# cSLIM_uSD.net
KiCad netlist of a schematic drawn in Altium Designer
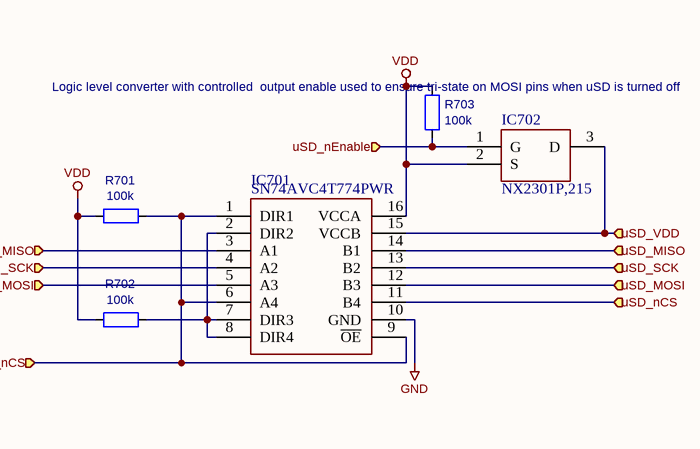
[diagram p0: cSLIM_uSD.SchDoc]

(export (version "E")
  (design (tool "Eeschema 10.0.6"))
  (components
    (comp (ref "IC701")
      (value "SN74AVC4T774PWR")
      (footprint "cSLIM-SA:SOP65P640X120-16N")
      (description "Integrated Circuit")
      (fields (field (name "MOUSER PART NUMBER") "595-SN74AVC4T774PWR"))
      (libsource (lib "cSLIM-SA") (part "SN74AVC4T774PWR"))
    )
    (comp (ref "IC702")
      (value "NX2301P,215")
      (footprint "cSLIM-SA:SOT95P230X110-3N")
      (description "Integrated Circuit")
      (fields (field (name "MOUSER PART NUMBER") "771-NX2301P215"))
      (libsource (lib "cSLIM-SA") (part "NX2301P,215"))
    )
    (comp (ref "R701") (value "100k") (footprint "RESC1608X55N") (libsource (lib "cSLIM-SA") (part "R")))
    (comp (ref "R702") (value "100k") (footprint "RESC1608X55N") (libsource (lib "cSLIM-SA") (part "R")))
    (comp (ref "R703") (value "100k") (footprint "RESC1608X55N") (libsource (lib "") (part "R_1")))
  )
  (nets
    (net (code "1") (name "/SPI_MISO") (class "Default")
      (node (ref "IC701") (pin "3") (pinfunction "A1_3") (pintype "passive"))
    )
    (net (code "2") (name "/SPI_MOSI") (class "Default")
      (node (ref "IC701") (pin "5") (pinfunction "A3_5") (pintype "passive"))
    )
    (net (code "3") (name "/SPI_SCK") (class "Default")
      (node (ref "IC701") (pin "4") (pinfunction "A2_4") (pintype "passive"))
    )
    (net (code "4") (name "/nRF_uSD_nCS") (class "Default")
      (node (ref "IC701") (pin "1") (pinfunction "DIR1_1") (pintype "passive"))
      (node (ref "IC701") (pin "6") (pinfunction "A4_6") (pintype "passive"))
      (node (ref "IC701") (pin "9") (pinfunction "~{OE}_9") (pintype "passive"))
      (node (ref "R701") (pin "1") (pinfunction "1_1") (pintype "passive"))
    )
    (net (code "5") (name "/uSD_MISO") (class "Default")
      (node (ref "IC701") (pin "14") (pinfunction "B1_14") (pintype "passive"))
    )
    (net (code "6") (name "/uSD_MOSI") (class "Default")
      (node (ref "IC701") (pin "12") (pinfunction "B3_12") (pintype "passive"))
    )
    (net (code "7") (name "/uSD_SCK") (class "Default")
      (node (ref "IC701") (pin "13") (pinfunction "B2_13") (pintype "passive"))
    )
    (net (code "8") (name "/uSD_VDD") (class "Default")
      (node (ref "IC701") (pin "15") (pinfunction "VCCB_15") (pintype "passive"))
      (node (ref "IC702") (pin "3") (pinfunction "D_3") (pintype "passive"))
    )
    (net (code "9") (name "/uSD_nCS") (class "Default")
      (node (ref "IC701") (pin "11") (pinfunction "B4_11") (pintype "passive"))
    )
    (net (code "10") (name "/uSD_nEnable") (class "Default")
      (node (ref "IC702") (pin "1") (pinfunction "G_1") (pintype "passive"))
      (node (ref "R703") (pin "1") (pinfunction "1_1") (pintype "passive"))
    )
    (net (code "11") (name "GND") (class "Default")
      (node (ref "IC701") (pin "10") (pinfunction "GND_10") (pintype "passive"))
    )
    (net (code "12") (name "Net-(IC701-DIR2)") (class "Default")
      (node (ref "IC701") (pin "2") (pinfunction "DIR2_2") (pintype "passive"))
      (node (ref "IC701") (pin "7") (pinfunction "DIR3_7") (pintype "passive"))
      (node (ref "IC701") (pin "8") (pinfunction "DIR4_8") (pintype "passive"))
      (node (ref "R702") (pin "1") (pinfunction "1_1") (pintype "passive"))
    )
    (net (code "13") (name "VDD") (class "Default")
      (node (ref "IC701") (pin "16") (pinfunction "VCCA_16") (pintype "passive"))
      (node (ref "IC702") (pin "2") (pinfunction "S_2") (pintype "passive"))
      (node (ref "R701") (pin "2") (pinfunction "2_2") (pintype "passive"))
      (node (ref "R702") (pin "2") (pinfunction "2_2") (pintype "passive"))
      (node (ref "R703") (pin "2") (pinfunction "2_2") (pintype "passive"))
    )
  )
)
